# brake_driver.net
KiCad netlist of a schematic drawn in Altium Designer
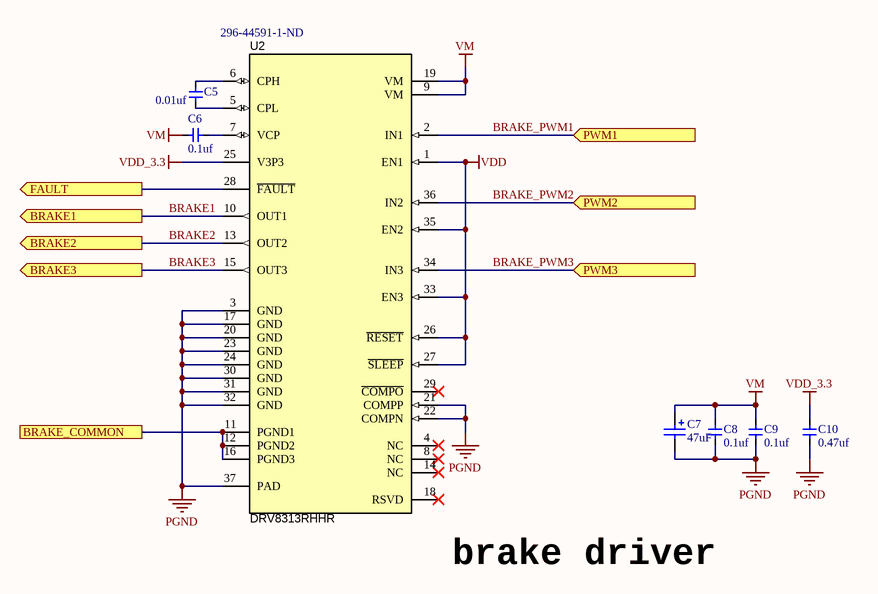
[diagram p0: brake_driver.SchDoc]

(export (version "E")
  (design (tool "Eeschema 10.0.6"))
  (components
    (comp (ref "C5")
      (value "0.01uf")
      (footprint "PCB_PassiveCap:CAP_0402")
      (description "Capacitor")
      (fields (field (name "Comment") "Cap_0402"))
      (libsource (lib "SCH_Passive") (part "Cap_0402"))
    )
    (comp (ref "C6")
      (value "0.1uf")
      (footprint "PCB_PassiveCap:CAP_0402")
      (description "Capacitor")
      (fields (field (name "Comment") "Cap_0402"))
      (libsource (lib "SCH_Passive") (part "Cap_0402"))
    )
    (comp (ref "C7")
      (value "47uF")
      (footprint "WCAP-PSLC_10x12.4")
      (description "WCAP-PSLC Aluminum Polymer Capacitors, size Ф10x12.4mm, 63V DC, 47uF")
      (fields
        (field (name "PART NUMBER") "875075761005")
        (field (name "Comment") "PSEF124470M063DVCTFB000")
        (field (name "PUBLISHER") "Wurth Elektronik")
      )
      (libsource (lib "ALTIUM-WCAP-PSLC-rev17b") (part "875075761005"))
    )
    (comp (ref "C8")
      (value "0.1uf")
      (footprint "PCB_PassiveCap:CAP_0402")
      (description "Capacitor")
      (fields (field (name "Comment") "Cap_0402"))
      (libsource (lib "SCH_Passive") (part "Cap_0402"))
    )
    (comp (ref "C9")
      (value "0.1uf")
      (footprint "PCB_PassiveCap:CAP_0402")
      (description "Capacitor")
      (fields (field (name "Comment") "Cap_0402"))
      (libsource (lib "SCH_Passive") (part "Cap_0402"))
    )
    (comp (ref "C10")
      (value "0.47uf")
      (footprint "PCB_PassiveCap:CAP_0402")
      (description "Capacitor")
      (fields (field (name "Comment") "Cap_0402"))
      (libsource (lib "SCH_Passive") (part "Cap_0402"))
    )
    (comp (ref "U2")
      (value "DRV8313RHHR")
      (footprint "RHH0036C")
      (description "2.5-A Triple 1/2-H Bridge Driver, RHH0036C")
      (fields
        (field (name "ALTERNATE PARTNUMBER") "DRV8313RHH")
        (field (name "MANUFACTURER") "Texas Instruments")
        (field (name "SUPPLIER PART NUMBER 1") "296-44591-1-ND")
        (field (name "SYMBOLCREATOR") "Altium")
        (field (name "PUBLISHER") "Texas Instruments")
      )
      (libsource (lib "dmib-s-power") (part "DRV8313RHHR"))
    )
  )
  (nets
    (net (code "1") (name "/BRAKE1") (class "Default")
      (node (ref "U2") (pin "10") (pinfunction "OUT1_10") (pintype "output"))
    )
    (net (code "2") (name "/BRAKE2") (class "Default")
      (node (ref "U2") (pin "13") (pinfunction "OUT2_13") (pintype "output"))
    )
    (net (code "3") (name "/BRAKE3") (class "Default")
      (node (ref "U2") (pin "15") (pinfunction "OUT3_15") (pintype "output"))
    )
    (net (code "4") (name "/BRAKE_COMMON") (class "Default")
      (node (ref "U2") (pin "11") (pinfunction "PGND1_11") (pintype "power_in"))
      (node (ref "U2") (pin "12") (pinfunction "PGND2_12") (pintype "power_in"))
      (node (ref "U2") (pin "16") (pinfunction "PGND3_16") (pintype "power_in"))
    )
    (net (code "5") (name "/BRAKE_PWM1") (class "Default")
      (node (ref "U2") (pin "2") (pinfunction "IN1_2") (pintype "input"))
    )
    (net (code "6") (name "/BRAKE_PWM2") (class "Default")
      (node (ref "U2") (pin "36") (pinfunction "IN2_36") (pintype "input"))
    )
    (net (code "7") (name "/BRAKE_PWM3") (class "Default")
      (node (ref "U2") (pin "34") (pinfunction "IN3_34") (pintype "input"))
    )
    (net (code "8") (name "/FAULT") (class "Default")
      (node (ref "U2") (pin "28") (pinfunction "FAULT_28") (pintype "open_collector"))
    )
    (net (code "9") (name "Net-(U2-CPH)") (class "Default")
      (node (ref "C5") (pin "2") (pinfunction "2_2") (pintype "passive"))
      (node (ref "U2") (pin "6") (pinfunction "CPH_6") (pintype "bidirectional"))
    )
    (net (code "10") (name "Net-(U2-CPL)") (class "Default")
      (node (ref "C5") (pin "1") (pinfunction "1_1") (pintype "passive"))
      (node (ref "U2") (pin "5") (pinfunction "CPL_5") (pintype "bidirectional"))
    )
    (net (code "11") (name "Net-(U2-VCP)") (class "Default")
      (node (ref "C6") (pin "2") (pinfunction "2_2") (pintype "passive"))
      (node (ref "U2") (pin "7") (pinfunction "VCP_7") (pintype "bidirectional"))
    )
    (net (code "12") (name "PGND") (class "Default")
      (node (ref "C10") (pin "2") (pinfunction "2_2") (pintype "passive"))
      (node (ref "C7") (pin "2") (pinfunction "N_2") (pintype "passive"))
      (node (ref "C8") (pin "2") (pinfunction "2_2") (pintype "passive"))
      (node (ref "C9") (pin "2") (pinfunction "2_2") (pintype "passive"))
      (node (ref "U2") (pin "17") (pinfunction "GND_17") (pintype "power_in"))
      (node (ref "U2") (pin "20") (pinfunction "GND_20") (pintype "power_in"))
      (node (ref "U2") (pin "21") (pinfunction "COMPP_21") (pintype "input"))
      (node (ref "U2") (pin "22") (pinfunction "COMPN_22") (pintype "input"))
      (node (ref "U2") (pin "23") (pinfunction "GND_23") (pintype "power_in"))
      (node (ref "U2") (pin "24") (pinfunction "GND_24") (pintype "power_in"))
      (node (ref "U2") (pin "3") (pinfunction "GND_3") (pintype "power_in"))
      (node (ref "U2") (pin "30") (pinfunction "GND_30") (pintype "power_in"))
      (node (ref "U2") (pin "31") (pinfunction "GND_31") (pintype "power_in"))
      (node (ref "U2") (pin "32") (pinfunction "GND_32") (pintype "power_in"))
      (node (ref "U2") (pin "37") (pinfunction "PAD_37") (pintype "power_in"))
    )
    (net (code "13") (name "VDD") (class "Default")
      (node (ref "U2") (pin "1") (pinfunction "EN1_1") (pintype "input"))
      (node (ref "U2") (pin "26") (pinfunction "RESET_26") (pintype "input"))
      (node (ref "U2") (pin "27") (pinfunction "SLEEP_27") (pintype "input"))
      (node (ref "U2") (pin "33") (pinfunction "EN3_33") (pintype "input"))
      (node (ref "U2") (pin "35") (pinfunction "EN2_35") (pintype "input"))
    )
    (net (code "14") (name "VDD_3.3") (class "Default")
      (node (ref "C10") (pin "1") (pinfunction "1_1") (pintype "passive"))
      (node (ref "U2") (pin "25") (pinfunction "V3P3_25") (pintype "power_in"))
    )
    (net (code "15") (name "VM") (class "Default")
      (node (ref "C6") (pin "1") (pinfunction "1_1") (pintype "passive"))
      (node (ref "C7") (pin "1") (pinfunction "P_1") (pintype "passive"))
      (node (ref "C8") (pin "1") (pinfunction "1_1") (pintype "passive"))
      (node (ref "C9") (pin "1") (pinfunction "1_1") (pintype "passive"))
      (node (ref "U2") (pin "19") (pinfunction "VM_19") (pintype "power_in"))
      (node (ref "U2") (pin "9") (pinfunction "VM_9") (pintype "power_in"))
    )
    (net (code "16") (name "unconnected-(U2-COMPO-Pad29)") (class "Default")
      (node (ref "U2") (pin "29") (pinfunction "COMPO_29") (pintype "open_collector+no_connect"))
    )
    (net (code "17") (name "unconnected-(U2-NC-Pad4)") (class "Default")
      (node (ref "U2") (pin "4") (pinfunction "NC_4") (pintype "passive+no_connect"))
    )
    (net (code "18") (name "unconnected-(U2-NC-Pad8)") (class "Default")
      (node (ref "U2") (pin "8") (pinfunction "NC_8") (pintype "passive+no_connect"))
    )
    (net (code "19") (name "unconnected-(U2-NC-Pad14)") (class "Default")
      (node (ref "U2") (pin "14") (pinfunction "NC_14") (pintype "passive+no_connect"))
    )
    (net (code "20") (name "unconnected-(U2-RSVD-Pad18)") (class "Default")
      (node (ref "U2") (pin "18") (pinfunction "RSVD_18") (pintype "passive+no_connect"))
    )
  )
)
